# Power.net
KiCad netlist of a schematic drawn in Altium Designer
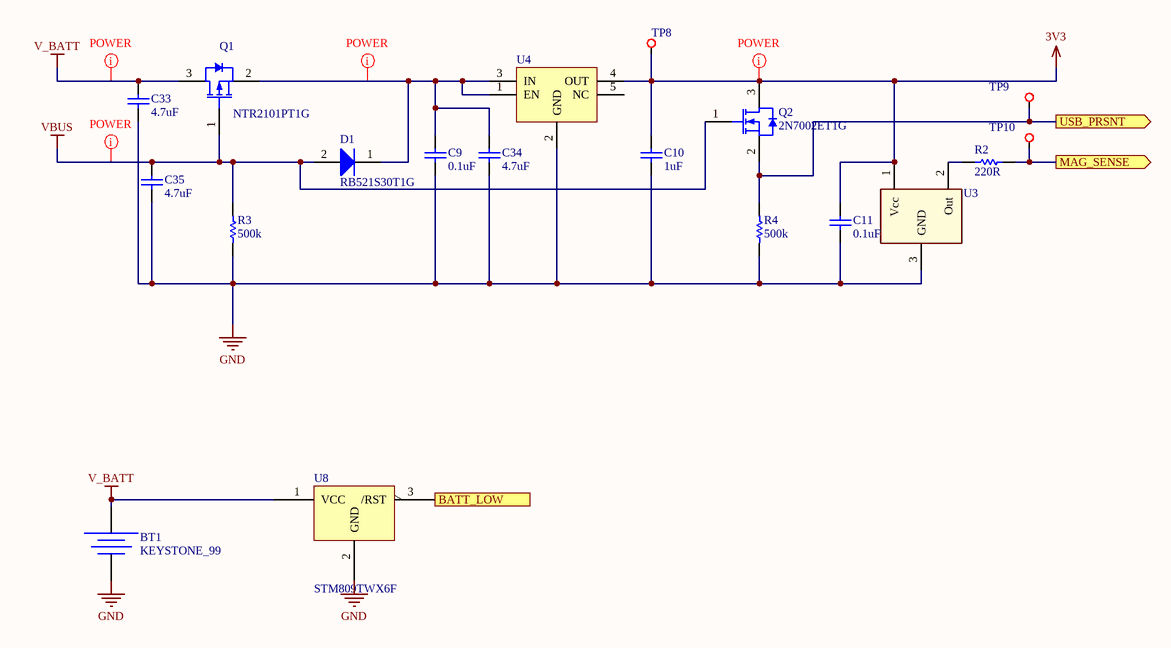
[diagram p0: Power.SchDoc]

(export (version "E")
  (design (tool "Eeschema 10.0.6"))
  (components
    (comp (ref "BT1")
      (value "KEYSTONE_99")
      (footprint "KEYSTONE_99")
      (libsource (lib "lib-Connectors") (part "KEYSTONE_99"))
    )
    (comp (ref "C9")
      (value "0.1uF")
      (footprint "0402cap")
      (description "0402 Ceramic Chip Capacitor - Standard")
      (fields (field (name "Comment") "C0402"))
      (libsource (lib "lib-Standard") (part "C0402"))
    )
    (comp (ref "C10")
      (value "1uF")
      (footprint "0402cap")
      (description "0402 Ceramic Chip Capacitor - Standard")
      (fields (field (name "Comment") "C0402"))
      (libsource (lib "Chip Capacitor") (part "C0402"))
    )
    (comp (ref "C11")
      (value "0.1uF")
      (footprint "0402cap")
      (description "0402 Ceramic Chip Capacitor - Standard")
      (fields (field (name "Comment") "C0402"))
      (libsource (lib "lib-Standard") (part "C0402"))
    )
    (comp (ref "C33")
      (value "4.7uF")
      (footprint "0603CAP")
      (description "0603 Ceramic Chip Capacitor - Standard")
      (fields (field (name "Comment") "C0603"))
      (libsource (lib "lib-Standard") (part "C0603"))
    )
    (comp (ref "C34")
      (value "4.7uF")
      (footprint "0603CAP")
      (description "0603 Ceramic Chip Capacitor - Standard")
      (fields (field (name "Comment") "C0603"))
      (libsource (lib "lib-Standard") (part "C0603"))
    )
    (comp (ref "C35")
      (value "4.7uF")
      (footprint "0603CAP")
      (description "0603 Ceramic Chip Capacitor - Standard")
      (fields (field (name "Comment") "C0603"))
      (libsource (lib "lib-Standard") (part "C0603"))
    )
    (comp (ref "D1")
      (value "RB521S30T1G")
      (footprint "ONSC-SOD-523-2-502-01_V")
      (description "Schottky Barrier Diode, 2-Pin SOD-523, Pb-Free, Tape and Reel")
      (fields (field (name "MANUFACTURER") "On Semiconductor"))
      (libsource (lib "Altium Content Vault") (part "ONSC-D-K1A2-2"))
    )
    (comp (ref "Q1")
      (value "NTR2101PT1G")
      (footprint "ONSC-SOT-23-3-318-08_V")
      (description "Small Signal MOSFET, -8 V, -3.7 A, Single P-Channel, 3-Pin SOT-23, Pb-Free, Tape and Reel")
      (libsource (lib "ON Semi MOSFETs") (part "NTR2101PT1G"))
    )
    (comp (ref "Q2")
      (value "2N7002ET1G")
      (footprint "ONSC-SOT-23-3-318-08_V")
      (description "Small Signal MOSFET, 60 V, 310 mA, Single, N-Channel, 3-Pin SOT-23, Pb-Free, Tape and Reel")
      (fields (field (name "MANUFACTURER") "On Semiconductor"))
      (libsource (lib "ON Semi MOSFETs") (part "2N7002ET1G"))
    )
    (comp (ref "R2")
      (value "220R")
      (footprint "0402RES")
      (description "0402 Chip Resistor - Standard")
      (fields (field (name "Comment") "R0402"))
      (libsource (lib "Chip Resistor") (part "R0402"))
    )
    (comp (ref "R3")
      (value "500k")
      (footprint "0402RES")
      (description "0402 Chip Resistor - Standard")
      (fields (field (name "Comment") "R0402"))
      (libsource (lib "Chip Resistor") (part "R0402"))
    )
    (comp (ref "R4")
      (value "500k")
      (footprint "0402RES")
      (description "0402 Chip Resistor - Standard")
      (fields (field (name "Comment") "R0402"))
      (libsource (lib "Chip Resistor") (part "R0402"))
    )
    (comp (ref "TP8")
      (value "TESTPOINT")
      (footprint "TP R25")
      (description "0.025\" Round Test Point")
      (fields (field (name "PART NUMBER") "1613"))
      (libsource (lib "TestPoints") (part "TP25"))
    )
    (comp (ref "TP9")
      (value "TESTPOINT")
      (footprint "TP R25")
      (description "0.025\" Round Test Point")
      (fields (field (name "PART NUMBER") "1613"))
      (libsource (lib "TestPoints") (part "TP25"))
    )
    (comp (ref "TP10")
      (value "TESTPOINT")
      (footprint "TP R25")
      (description "0.025\" Round Test Point")
      (fields (field (name "PART NUMBER") "1613"))
      (libsource (lib "TestPoints") (part "TP25"))
    )
    (comp (ref "U3")
      (value "DRV5032FBDBZT")
      (footprint "SOT-23")
      (description "Hall Effect Sensor")
      (libsource (lib "VHF Library") (part "DRV5032FBDBZT"))
    )
    (comp (ref "U4")
      (value "IC REG LINEAR 3.3V 200MA ESV")
      (footprint "TCR2EE33,LM(CT")
      (description "Linear Voltage Regulator IC Positive Fixed 1 Output  200mA ESV")
      (libsource (lib "lib-VoltageRegulators") (part "TCR2EE33,LM(CT"))
    )
    (comp (ref "U8")
      (value "STM809TWX6F")
      (footprint "SOT103P237X112-3N")
      (description "IC MPU RESET CIRC 3.08V SOT23")
      (libsource (lib "lib-IC_Other") (part "STM809TWX6F"))
    )
  )
  (nets
    (net (code "1") (name "/BATT_LOW") (class "Default")
      (node (ref "U8") (pin "3") (pinfunction "/RST_3") (pintype "passive"))
    )
    (net (code "2") (name "/MAG_SENSE") (class "Default")
      (node (ref "R2") (pin "2") (pinfunction "2_2") (pintype "passive"))
      (node (ref "TP10") (pin "1") (pinfunction "1_1") (pintype "passive"))
    )
    (net (code "3") (name "/USB_PRSNT") (class "Default")
      (node (ref "Q2") (pin "2") (pinfunction "S_2") (pintype "passive"))
      (node (ref "R4") (pin "2") (pinfunction "2_2") (pintype "passive"))
      (node (ref "TP9") (pin "1") (pinfunction "1_1") (pintype "passive"))
    )
    (net (code "4") (name "3V3") (class "Default")
      (node (ref "C10") (pin "2") (pinfunction "2_2") (pintype "passive"))
      (node (ref "C11") (pin "2") (pinfunction "2_2") (pintype "passive"))
      (node (ref "Q2") (pin "3") (pinfunction "D_3") (pintype "passive"))
      (node (ref "TP8") (pin "1") (pinfunction "1_1") (pintype "passive"))
      (node (ref "U3") (pin "1") (pinfunction "Vcc_1") (pintype "passive"))
      (node (ref "U4") (pin "4") (pinfunction "OUT_4") (pintype "passive"))
    )
    (net (code "5") (name "GND") (class "Default")
      (node (ref "BT1") (pin "2") (pinfunction "NEG_2") (pintype "passive"))
      (node (ref "C10") (pin "1") (pinfunction "1_1") (pintype "passive"))
      (node (ref "C11") (pin "1") (pinfunction "1_1") (pintype "passive"))
      (node (ref "C33") (pin "1") (pinfunction "1_1") (pintype "passive"))
      (node (ref "C34") (pin "1") (pinfunction "1_1") (pintype "passive"))
      (node (ref "C35") (pin "1") (pinfunction "1_1") (pintype "passive"))
      (node (ref "C9") (pin "1") (pinfunction "1_1") (pintype "passive"))
      (node (ref "R3") (pin "1") (pinfunction "1_1") (pintype "passive"))
      (node (ref "R4") (pin "1") (pinfunction "1_1") (pintype "passive"))
      (node (ref "U3") (pin "3") (pinfunction "GND_3") (pintype "passive"))
      (node (ref "U4") (pin "2") (pinfunction "GND_2") (pintype "passive"))
      (node (ref "U8") (pin "2") (pinfunction "GND_2") (pintype "passive"))
    )
    (net (code "6") (name "Net-(D1-K)") (class "Default")
      (node (ref "C34") (pin "2") (pinfunction "2_2") (pintype "passive"))
      (node (ref "C9") (pin "2") (pinfunction "2_2") (pintype "passive"))
      (node (ref "D1") (pin "1") (pinfunction "K_1") (pintype "passive"))
      (node (ref "Q1") (pin "2") (pinfunction "S_2") (pintype "passive"))
      (node (ref "U4") (pin "1") (pinfunction "EN_1") (pintype "passive"))
      (node (ref "U4") (pin "3") (pinfunction "IN_3") (pintype "passive"))
    )
    (net (code "7") (name "Net-(U3-Out)") (class "Default")
      (node (ref "R2") (pin "1") (pinfunction "1_1") (pintype "passive"))
      (node (ref "U3") (pin "2") (pinfunction "Out_2") (pintype "passive"))
    )
    (net (code "8") (name "VBUS") (class "Default")
      (node (ref "C35") (pin "2") (pinfunction "2_2") (pintype "passive"))
      (node (ref "D1") (pin "2") (pinfunction "A_2") (pintype "passive"))
      (node (ref "Q1") (pin "1") (pinfunction "G_1") (pintype "passive"))
      (node (ref "Q2") (pin "1") (pinfunction "G_1") (pintype "passive"))
      (node (ref "R3") (pin "2") (pinfunction "2_2") (pintype "passive"))
    )
    (net (code "9") (name "V_BATT") (class "Default")
      (node (ref "BT1") (pin "1") (pinfunction "POS_1") (pintype "passive"))
      (node (ref "C33") (pin "2") (pinfunction "2_2") (pintype "passive"))
      (node (ref "Q1") (pin "3") (pinfunction "D_3") (pintype "passive"))
      (node (ref "U8") (pin "1") (pinfunction "VCC_1") (pintype "passive"))
    )
    (net (code "10") (name "unconnected-(U4-NC-Pad5)") (class "Default")
      (node (ref "U4") (pin "5") (pinfunction "NC_5") (pintype "passive"))
    )
  )
)
